# Power.net
KiCad netlist of a schematic drawn in Altium Designer
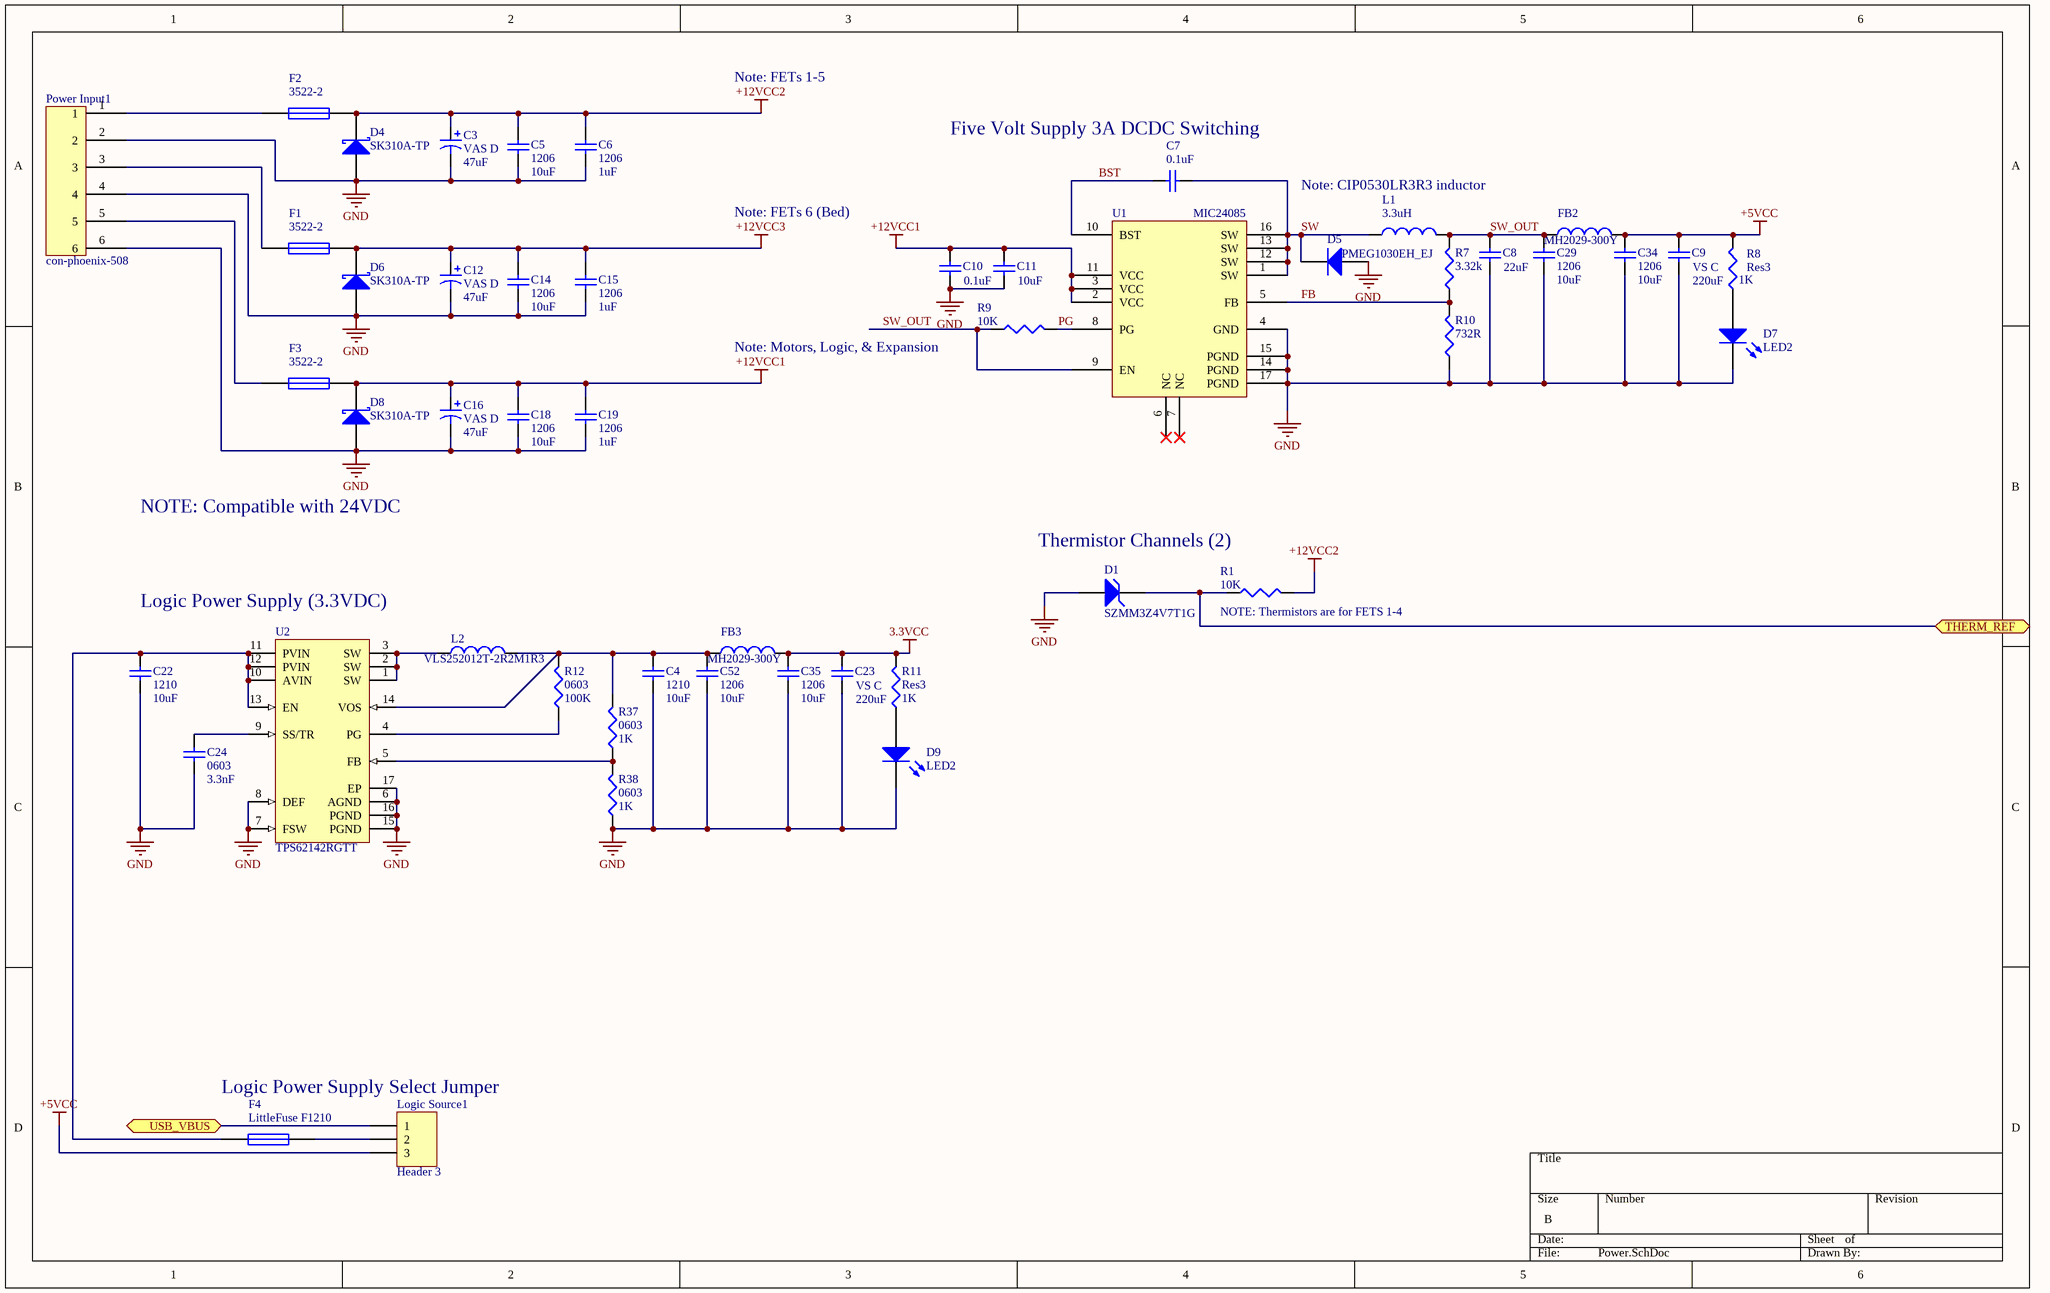
[diagram p0: Power.SchDoc]

(export (version "E")
  (design (tool "Eeschema 10.0.6"))
  (components
    (comp (ref "C3")
      (value "VAS D")
      (footprint "Panasonic VS D")
      (description "Polarized Capacitor (Radial)")
      (fields (field (name "ALTIUM_VALUE") "47uF") (field (name "PUBLISHER") "Altium Limited"))
      (libsource (lib "Miscellaneous Devices") (part "Cap Pol1"))
    )
    (comp (ref "C4")
      (value "1210")
      (footprint "C1210")
      (description "Capacitor (Semiconductor SIM Model)")
      (fields (field (name "ALTIUM_VALUE") "10uF") (field (name "PUBLISHER") "Altium Limited"))
      (libsource (lib "Miscellaneous Devices") (part "Cap Semi"))
    )
    (comp (ref "C5")
      (value "1206")
      (footprint "C1206")
      (description "Capacitor (Semiconductor SIM Model)")
      (fields (field (name "ALTIUM_VALUE") "10uF") (field (name "PUBLISHER") "Altium Limited"))
      (libsource (lib "Miscellaneous Devices") (part "Cap Semi"))
    )
    (comp (ref "C6")
      (value "1206")
      (footprint "C1206")
      (description "Capacitor (Semiconductor SIM Model)")
      (fields (field (name "ALTIUM_VALUE") "1uF") (field (name "PUBLISHER") "Altium Limited"))
      (libsource (lib "Miscellaneous Devices") (part "Cap Semi"))
    )
    (comp (ref "C7")
      (value "0.1uF")
      (footprint "1608[0603]")
      (description "Capacitor (Semiconductor SIM Model)")
      (fields (field (name "Comment") "Cap Semi") (field (name "PUBLISHER") "Altium Limited"))
      (libsource (lib "Miscellaneous Devices") (part "Cap Semi"))
    )
    (comp (ref "C8")
      (value "22uF")
      (footprint "C1206")
      (description "Capacitor (Semiconductor SIM Model)")
      (fields (field (name "Comment") "Cap Semi") (field (name "PUBLISHER") "Altium Limited"))
      (libsource (lib "Miscellaneous Devices") (part "Cap Semi"))
    )
    (comp (ref "C9")
      (value "VS C")
      (footprint "Panasonic VS C")
      (description "Capacitor (Semiconductor SIM Model)")
      (fields (field (name "ALTIUM_VALUE") "220uF") (field (name "PUBLISHER") "Altium Limited"))
      (libsource (lib "Miscellaneous Devices") (part "Cap Semi"))
    )
    (comp (ref "C10")
      (value "0.1uF")
      (footprint "C1206")
      (description "Capacitor (Semiconductor SIM Model)")
      (fields (field (name "Comment") "Cap Semi") (field (name "PUBLISHER") "Altium Limited"))
      (libsource (lib "Miscellaneous Devices") (part "Cap Semi"))
    )
    (comp (ref "C11")
      (value "10uF")
      (footprint "1608[0603]")
      (description "Capacitor (Semiconductor SIM Model)")
      (fields (field (name "Comment") "Cap Semi") (field (name "PUBLISHER") "Altium Limited"))
      (libsource (lib "Miscellaneous Devices") (part "Cap Semi"))
    )
    (comp (ref "C12")
      (value "VAS D")
      (footprint "Panasonic VS D")
      (description "Polarized Capacitor (Radial)")
      (fields (field (name "ALTIUM_VALUE") "47uF") (field (name "PUBLISHER") "Altium Limited"))
      (libsource (lib "Miscellaneous Devices") (part "Cap Pol1"))
    )
    (comp (ref "C14")
      (value "1206")
      (footprint "C1206")
      (description "Capacitor (Semiconductor SIM Model)")
      (fields (field (name "ALTIUM_VALUE") "10uF") (field (name "PUBLISHER") "Altium Limited"))
      (libsource (lib "Miscellaneous Devices") (part "Cap Semi"))
    )
    (comp (ref "C15")
      (value "1206")
      (footprint "C1206")
      (description "Capacitor (Semiconductor SIM Model)")
      (fields (field (name "ALTIUM_VALUE") "1uF") (field (name "PUBLISHER") "Altium Limited"))
      (libsource (lib "Miscellaneous Devices") (part "Cap Semi"))
    )
    (comp (ref "C16")
      (value "VAS D")
      (footprint "Panasonic VS D")
      (description "Polarized Capacitor (Radial)")
      (fields (field (name "ALTIUM_VALUE") "47uF") (field (name "PUBLISHER") "Altium Limited"))
      (libsource (lib "Miscellaneous Devices") (part "Cap Pol1"))
    )
    (comp (ref "C18")
      (value "1206")
      (footprint "C1206")
      (description "Capacitor (Semiconductor SIM Model)")
      (fields (field (name "ALTIUM_VALUE") "10uF") (field (name "PUBLISHER") "Altium Limited"))
      (libsource (lib "Miscellaneous Devices") (part "Cap Semi"))
    )
    (comp (ref "C19")
      (value "1206")
      (footprint "C1206")
      (description "Capacitor (Semiconductor SIM Model)")
      (fields (field (name "ALTIUM_VALUE") "1uF") (field (name "PUBLISHER") "Altium Limited"))
      (libsource (lib "Miscellaneous Devices") (part "Cap Semi"))
    )
    (comp (ref "C22")
      (value "1210")
      (footprint "C1210")
      (description "Capacitor (Semiconductor SIM Model)")
      (fields (field (name "ALTIUM_VALUE") "10uF") (field (name "PUBLISHER") "Altium Limited"))
      (libsource (lib "Miscellaneous Devices") (part "Cap Semi"))
    )
    (comp (ref "C23")
      (value "VS C")
      (footprint "Panasonic VS C")
      (description "Capacitor (Semiconductor SIM Model)")
      (fields (field (name "ALTIUM_VALUE") "220uF") (field (name "PUBLISHER") "Altium Limited"))
      (libsource (lib "Miscellaneous Devices") (part "Cap Semi"))
    )
    (comp (ref "C24")
      (value "0603")
      (footprint "1608[0603]")
      (description "Capacitor (Semiconductor SIM Model)")
      (fields (field (name "ALTIUM_VALUE") "3.3nF") (field (name "PUBLISHER") "Altium Limited"))
      (libsource (lib "Miscellaneous Devices") (part "Cap Semi"))
    )
    (comp (ref "C29")
      (value "1206")
      (footprint "C1206")
      (description "Capacitor (Semiconductor SIM Model)")
      (fields (field (name "ALTIUM_VALUE") "10uF") (field (name "PUBLISHER") "Altium Limited"))
      (libsource (lib "Miscellaneous Devices") (part "Cap Semi"))
    )
    (comp (ref "C34")
      (value "1206")
      (footprint "C1206")
      (description "Capacitor (Semiconductor SIM Model)")
      (fields (field (name "ALTIUM_VALUE") "10uF") (field (name "PUBLISHER") "Altium Limited"))
      (libsource (lib "Miscellaneous Devices") (part "Cap Semi"))
    )
    (comp (ref "C35")
      (value "1206")
      (footprint "C1206")
      (description "Capacitor (Semiconductor SIM Model)")
      (fields (field (name "ALTIUM_VALUE") "10uF") (field (name "PUBLISHER") "Altium Limited"))
      (libsource (lib "Miscellaneous Devices") (part "Cap Semi"))
    )
    (comp (ref "C52")
      (value "1206")
      (footprint "C1206")
      (description "Capacitor (Semiconductor SIM Model)")
      (fields (field (name "ALTIUM_VALUE") "10uF") (field (name "PUBLISHER") "Altium Limited"))
      (libsource (lib "Miscellaneous Devices") (part "Cap Semi"))
    )
    (comp (ref "D1")
      (value "SZMM3Z4V7T1G")
      (footprint "SZMM3Z4V7T1G")
      (description "Zener Diode")
      (fields (field (name "PUBLISHER") "Altium Limited"))
      (libsource (lib "Miscellaneous Devices") (part "D Zener"))
    )
    (comp (ref "D4")
      (value "SK310A-TP")
      (footprint "SK310A-TP")
      (description "Schottky Diode")
      (fields (field (name "PUBLISHER") "Altium Limited"))
      (libsource (lib "Miscellaneous Devices") (part "D Schottky"))
    )
    (comp (ref "D5")
      (value "PMEG1030EH_EJ")
      (footprint "PMEG1030EH_EJ")
      (description "Default Diode")
      (fields (field (name "PUBLISHER") "Altium Limited"))
      (libsource (lib "ZMBo Schematic Library") (part "PMEG1030EH_EJ"))
    )
    (comp (ref "D6")
      (value "SK310A-TP")
      (footprint "SK310A-TP")
      (description "Schottky Diode")
      (fields (field (name "PUBLISHER") "Altium Limited"))
      (libsource (lib "Miscellaneous Devices") (part "D Schottky"))
    )
    (comp (ref "D7")
      (value "LED2")
      (footprint "SM 0805 polarized")
      (description "Typical RED, GREEN, YELLOW, AMBER GaAs LED")
      (fields (field (name "PUBLISHER") "Altium Limited"))
      (libsource (lib "Miscellaneous Devices") (part "LED2"))
    )
    (comp (ref "D8")
      (value "SK310A-TP")
      (footprint "SK310A-TP")
      (description "Schottky Diode")
      (fields (field (name "PUBLISHER") "Altium Limited"))
      (libsource (lib "Miscellaneous Devices") (part "D Schottky"))
    )
    (comp (ref "D9")
      (value "LED2")
      (footprint "SM 0805 polarized")
      (description "Typical RED, GREEN, YELLOW, AMBER GaAs LED")
      (fields (field (name "PUBLISHER") "Altium Limited"))
      (libsource (lib "Miscellaneous Devices") (part "LED2"))
    )
    (comp (ref "F1")
      (value "3522-2")
      (footprint "3522-2")
      (description "Fuse")
      (fields (field (name "PUBLISHER") "Altium Limited"))
      (libsource (lib "Miscellaneous Devices") (part "Fuse 1"))
    )
    (comp (ref "F2")
      (value "3522-2")
      (footprint "3522-2")
      (description "Fuse")
      (fields (field (name "PUBLISHER") "Altium Limited"))
      (libsource (lib "Miscellaneous Devices") (part "Fuse 1"))
    )
    (comp (ref "F3")
      (value "3522-2")
      (footprint "3522-2")
      (description "Fuse")
      (fields (field (name "PUBLISHER") "Altium Limited"))
      (libsource (lib "Miscellaneous Devices") (part "Fuse 1"))
    )
    (comp (ref "F4")
      (value "LittleFuse F1210")
      (footprint "F1210_M")
      (description "Fuse")
      (fields (field (name "PUBLISHER") "Altium Limited"))
      (libsource (lib "Miscellaneous Devices") (part "Fuse 1"))
    )
    (comp (ref "FB2")
      (value "MH2029-300Y")
      (footprint "SM 0805 - gap trimmed")
      (description "Inductor")
      (fields (field (name "PUBLISHER") "Altium Limited"))
      (libsource (lib "Miscellaneous Devices") (part "Inductor"))
    )
    (comp (ref "FB3")
      (value "MH2029-300Y")
      (footprint "SM 0805 - gap trimmed")
      (description "Inductor")
      (fields (field (name "PUBLISHER") "Altium Limited"))
      (libsource (lib "Miscellaneous Devices") (part "Inductor"))
    )
    (comp (ref "L1")
      (value "3.3uH")
      (footprint "CIP0530LR3R3")
      (description "Inductor")
      (fields (field (name "PUBLISHER") "Altium Limited"))
      (libsource (lib "Miscellaneous Devices") (part "Inductor"))
    )
    (comp (ref "L2")
      (value "VLS252012T-2R2M1R3")
      (footprint "VLS252012T-2R2M1R3")
      (description "Inductor")
      (fields (field (name "PUBLISHER") "Altium Limited"))
      (libsource (lib "Miscellaneous Devices") (part "Inductor"))
    )
    (comp (ref "Logic Source1")
      (value "Header 3")
      (footprint "HDR1X3")
      (description "Header, 3-Pin")
      (fields (field (name "PUBLISHER") "Altium Limited"))
      (libsource (lib "Miscellaneous Connectors") (part "Header 3"))
    )
    (comp (ref "Power Input1")
      (value "con-phoenix-508")
      (footprint "MSTBV6")
      (libsource (lib "RADMBo Schematic Library") (part "con-phoenix-508"))
    )
    (comp (ref "R1")
      (value "10K")
      (footprint "J1-0603")
      (description "Resistor")
      (fields (field (name "Comment") "Res3") (field (name "PUBLISHER") "Altium Limited"))
      (libsource (lib "Miscellaneous Devices") (part "Res3"))
    )
    (comp (ref "R7")
      (value "3.32k")
      (footprint "J1-0603")
      (description "Resistor")
      (fields (field (name "Comment") "Res3") (field (name "PUBLISHER") "Altium Limited"))
      (libsource (lib "Miscellaneous Devices") (part "Res3"))
    )
    (comp (ref "R8")
      (value "Res3")
      (footprint "SM 0805 - gap trimmed")
      (description "Resistor")
      (fields (field (name "ALTIUM_VALUE") "1K") (field (name "PUBLISHER") "Altium Limited"))
      (libsource (lib "Miscellaneous Devices") (part "Res3"))
    )
    (comp (ref "R9")
      (value "10K")
      (footprint "J1-0603")
      (description "Resistor")
      (fields (field (name "Comment") "Res3") (field (name "PUBLISHER") "Altium Limited"))
      (libsource (lib "Miscellaneous Devices") (part "Res3"))
    )
    (comp (ref "R10")
      (value "732R")
      (footprint "J1-0603")
      (description "Resistor")
      (fields (field (name "Comment") "Res3") (field (name "PUBLISHER") "Altium Limited"))
      (libsource (lib "Miscellaneous Devices") (part "Res3"))
    )
    (comp (ref "R11")
      (value "Res3")
      (footprint "SM 0805 - gap trimmed")
      (description "Resistor")
      (fields (field (name "ALTIUM_VALUE") "1K") (field (name "PUBLISHER") "Altium Limited"))
      (libsource (lib "Miscellaneous Devices") (part "Res3"))
    )
    (comp (ref "R12")
      (value "0603")
      (footprint "J1-0603")
      (description "Resistor")
      (fields (field (name "ALTIUM_VALUE") "100K") (field (name "PUBLISHER") "Altium Limited"))
      (libsource (lib "Miscellaneous Devices") (part "Res3"))
    )
    (comp (ref "R37")
      (value "0603")
      (footprint "J1-0603")
      (description "Resistor")
      (fields (field (name "ALTIUM_VALUE") "1K") (field (name "PUBLISHER") "Altium Limited"))
      (libsource (lib "Miscellaneous Devices") (part "Res3"))
    )
    (comp (ref "R38")
      (value "0603")
      (footprint "J1-0603")
      (description "Resistor")
      (fields (field (name "ALTIUM_VALUE") "1K") (field (name "PUBLISHER") "Altium Limited"))
      (libsource (lib "Miscellaneous Devices") (part "Res3"))
    )
    (comp (ref "U1")
      (value "MIC24085")
      (footprint "MIC24085-AYML")
      (libsource (lib "Adams Altium Library") (part "MIC24085"))
    )
    (comp (ref "U2")
      (value "TPS62142RGTT")
      (footprint "RGT16-1700X1700TP")
      (fields (field (name "MANUFACTURER") "Texas Instruments"))
      (libsource (lib "TI Power Management Step-Down Regulator") (part "TPS62142RGTT"))
    )
  )
  (nets
    (net (code "1") (name "+5VCC") (class "Default")
      (node (ref "C34") (pin "1") (pinfunction "1_1") (pintype "passive"))
      (node (ref "C9") (pin "1") (pinfunction "1_1") (pintype "passive"))
      (node (ref "FB2") (pin "2") (pinfunction "2_2") (pintype "passive"))
      (node (ref "Logic Source1") (pin "3") (pinfunction "3_3") (pintype "passive"))
      (node (ref "R8") (pin "2") (pinfunction "2_2") (pintype "passive"))
    )
    (net (code "2") (name "+12VCC1") (class "Default")
      (node (ref "C10") (pin "2") (pinfunction "2_2") (pintype "passive"))
      (node (ref "C11") (pin "2") (pinfunction "2_2") (pintype "passive"))
      (node (ref "C16") (pin "1") (pinfunction "1_1") (pintype "passive"))
      (node (ref "C18") (pin "2") (pinfunction "2_2") (pintype "passive"))
      (node (ref "C19") (pin "2") (pinfunction "2_2") (pintype "passive"))
      (node (ref "D8") (pin "2") (pinfunction "K_2") (pintype "passive"))
      (node (ref "F3") (pin "2") (pinfunction "2_2") (pintype "passive"))
      (node (ref "U1") (pin "11") (pinfunction "VCC_11") (pintype "passive"))
      (node (ref "U1") (pin "2") (pinfunction "VCC_2") (pintype "passive"))
      (node (ref "U1") (pin "3") (pinfunction "VCC_3") (pintype "passive"))
    )
    (net (code "3") (name "+12VCC2") (class "Default")
      (node (ref "C3") (pin "1") (pinfunction "1_1") (pintype "passive"))
      (node (ref "C5") (pin "2") (pinfunction "2_2") (pintype "passive"))
      (node (ref "C6") (pin "2") (pinfunction "2_2") (pintype "passive"))
      (node (ref "D4") (pin "2") (pinfunction "K_2") (pintype "passive"))
      (node (ref "F2") (pin "2") (pinfunction "2_2") (pintype "passive"))
      (node (ref "R1") (pin "2") (pinfunction "2_2") (pintype "passive"))
    )
    (net (code "4") (name "+12VCC3") (class "Default")
      (node (ref "C12") (pin "1") (pinfunction "1_1") (pintype "passive"))
      (node (ref "C14") (pin "2") (pinfunction "2_2") (pintype "passive"))
      (node (ref "C15") (pin "2") (pinfunction "2_2") (pintype "passive"))
      (node (ref "D6") (pin "2") (pinfunction "K_2") (pintype "passive"))
      (node (ref "F1") (pin "2") (pinfunction "2_2") (pintype "passive"))
    )
    (net (code "5") (name "/BST") (class "Default")
      (node (ref "C7") (pin "2") (pinfunction "2_2") (pintype "passive"))
      (node (ref "U1") (pin "10") (pinfunction "BST_10") (pintype "passive"))
    )
    (net (code "6") (name "/FB") (class "Default")
      (node (ref "R10") (pin "2") (pinfunction "2_2") (pintype "passive"))
      (node (ref "R7") (pin "1") (pinfunction "1_1") (pintype "passive"))
      (node (ref "U1") (pin "5") (pinfunction "FB_5") (pintype "passive"))
    )
    (net (code "7") (name "/PG") (class "Default")
      (node (ref "R9") (pin "2") (pinfunction "2_2") (pintype "passive"))
      (node (ref "U1") (pin "8") (pinfunction "PG_8") (pintype "passive"))
    )
    (net (code "8") (name "/SW") (class "Default")
      (node (ref "C7") (pin "1") (pinfunction "1_1") (pintype "passive"))
      (node (ref "D5") (pin "2") (pinfunction "K_2") (pintype "passive"))
      (node (ref "L1") (pin "1") (pinfunction "1_1") (pintype "passive"))
      (node (ref "U1") (pin "1") (pinfunction "SW_1") (pintype "passive"))
      (node (ref "U1") (pin "12") (pinfunction "SW_12") (pintype "passive"))
      (node (ref "U1") (pin "13") (pinfunction "SW_13") (pintype "passive"))
      (node (ref "U1") (pin "16") (pinfunction "SW_16") (pintype "passive"))
    )
    (net (code "9") (name "/SW_OUT") (class "Default")
      (node (ref "C29") (pin "1") (pinfunction "1_1") (pintype "passive"))
      (node (ref "C8") (pin "2") (pinfunction "2_2") (pintype "passive"))
      (node (ref "FB2") (pin "1") (pinfunction "1_1") (pintype "passive"))
      (node (ref "L1") (pin "2") (pinfunction "2_2") (pintype "passive"))
      (node (ref "R7") (pin "2") (pinfunction "2_2") (pintype "passive"))
      (node (ref "R9") (pin "1") (pinfunction "1_1") (pintype "passive"))
      (node (ref "U1") (pin "9") (pinfunction "EN_9") (pintype "passive"))
    )
    (net (code "10") (name "/THERM_REF") (class "Default")
      (node (ref "D1") (pin "2") (pinfunction "K_2") (pintype "passive"))
      (node (ref "R1") (pin "1") (pinfunction "1_1") (pintype "passive"))
    )
    (net (code "11") (name "/USB_VBUS") (class "Default")
      (node (ref "Logic Source1") (pin "1") (pinfunction "1_1") (pintype "passive"))
    )
    (net (code "12") (name "3.3VCC") (class "Default")
      (node (ref "C23") (pin "1") (pinfunction "1_1") (pintype "passive"))
      (node (ref "C35") (pin "1") (pinfunction "1_1") (pintype "passive"))
      (node (ref "FB3") (pin "2") (pinfunction "2_2") (pintype "passive"))
      (node (ref "R11") (pin "2") (pinfunction "2_2") (pintype "passive"))
    )
    (net (code "13") (name "GND") (class "Default")
      (node (ref "C10") (pin "1") (pinfunction "1_1") (pintype "passive"))
      (node (ref "C11") (pin "1") (pinfunction "1_1") (pintype "passive"))
      (node (ref "C12") (pin "2") (pinfunction "2_2") (pintype "passive"))
      (node (ref "C14") (pin "1") (pinfunction "1_1") (pintype "passive"))
      (node (ref "C15") (pin "1") (pinfunction "1_1") (pintype "passive"))
      (node (ref "C16") (pin "2") (pinfunction "2_2") (pintype "passive"))
      (node (ref "C18") (pin "1") (pinfunction "1_1") (pintype "passive"))
      (node (ref "C19") (pin "1") (pinfunction "1_1") (pintype "passive"))
      (node (ref "C22") (pin "2") (pinfunction "2_2") (pintype "passive"))
      (node (ref "C23") (pin "2") (pinfunction "2_2") (pintype "passive"))
      (node (ref "C24") (pin "1") (pinfunction "1_1") (pintype "passive"))
      (node (ref "C29") (pin "2") (pinfunction "2_2") (pintype "passive"))
      (node (ref "C3") (pin "2") (pinfunction "2_2") (pintype "passive"))
      (node (ref "C34") (pin "2") (pinfunction "2_2") (pintype "passive"))
      (node (ref "C35") (pin "2") (pinfunction "2_2") (pintype "passive"))
      (node (ref "C4") (pin "2") (pinfunction "2_2") (pintype "passive"))
      (node (ref "C5") (pin "1") (pinfunction "1_1") (pintype "passive"))
      (node (ref "C52") (pin "2") (pinfunction "2_2") (pintype "passive"))
      (node (ref "C6") (pin "1") (pinfunction "1_1") (pintype "passive"))
      (node (ref "C8") (pin "1") (pinfunction "1_1") (pintype "passive"))
      (node (ref "C9") (pin "2") (pinfunction "2_2") (pintype "passive"))
      (node (ref "D1") (pin "1") (pinfunction "A_1") (pintype "passive"))
      (node (ref "D4") (pin "1") (pinfunction "A_1") (pintype "passive"))
      (node (ref "D5") (pin "1") (pinfunction "A_1") (pintype "passive"))
      (node (ref "D6") (pin "1") (pinfunction "A_1") (pintype "passive"))
      (node (ref "D7") (pin "1") (pinfunction "A_1") (pintype "passive"))
      (node (ref "D8") (pin "1") (pinfunction "A_1") (pintype "passive"))
      (node (ref "D9") (pin "1") (pinfunction "A_1") (pintype "passive"))
      (node (ref "Power Input1") (pin "2") (pinfunction "2_2") (pintype "passive"))
      (node (ref "Power Input1") (pin "4") (pinfunction "4_4") (pintype "passive"))
      (node (ref "Power Input1") (pin "6") (pinfunction "6_6") (pintype "passive"))
      (node (ref "R10") (pin "1") (pinfunction "1_1") (pintype "passive"))
      (node (ref "R38") (pin "1") (pinfunction "1_1") (pintype "passive"))
      (node (ref "U1") (pin "14") (pinfunction "PGND_14") (pintype "passive"))
      (node (ref "U1") (pin "15") (pinfunction "PGND_15") (pintype "passive"))
      (node (ref "U1") (pin "17") (pinfunction "PGND_17") (pintype "passive"))
      (node (ref "U1") (pin "4") (pinfunction "GND_4") (pintype "passive"))
      (node (ref "U2") (pin "15") (pinfunction "PGND_15") (pintype "power_in"))
      (node (ref "U2") (pin "16") (pinfunction "PGND_16") (pintype "power_in"))
      (node (ref "U2") (pin "17") (pinfunction "EP_17") (pintype "power_in"))
      (node (ref "U2") (pin "6") (pinfunction "AGND_6") (pintype "power_in"))
      (node (ref "U2") (pin "7") (pinfunction "FSW_7") (pintype "input"))
      (node (ref "U2") (pin "8") (pinfunction "DEF_8") (pintype "input"))
    )
    (net (code "14") (name "Net-(D7-K)") (class "Default")
      (node (ref "D7") (pin "2") (pinfunction "K_2") (pintype "passive"))
      (node (ref "R8") (pin "1") (pinfunction "1_1") (pintype "passive"))
    )
    (net (code "15") (name "Net-(D9-K)") (class "Default")
      (node (ref "D9") (pin "2") (pinfunction "K_2") (pintype "passive"))
      (node (ref "R11") (pin "1") (pinfunction "1_1") (pintype "passive"))
    )
    (net (code "16") (name "Net-(F1-Pad1)") (class "Default")
      (node (ref "F1") (pin "1") (pinfunction "1_1") (pintype "passive"))
      (node (ref "Power Input1") (pin "3") (pinfunction "3_3") (pintype "passive"))
    )
    (net (code "17") (name "Net-(F2-Pad1)") (class "Default")
      (node (ref "F2") (pin "1") (pinfunction "1_1") (pintype "passive"))
      (node (ref "Power Input1") (pin "1") (pinfunction "1_1") (pintype "passive"))
    )
    (net (code "18") (name "Net-(F3-Pad1)") (class "Default")
      (node (ref "F3") (pin "1") (pinfunction "1_1") (pintype "passive"))
      (node (ref "Power Input1") (pin "5") (pinfunction "5_5") (pintype "passive"))
    )
    (net (code "19") (name "Net-(F4-Pad2)") (class "Default")
      (node (ref "F4") (pin "2") (pinfunction "2_2") (pintype "passive"))
      (node (ref "Logic Source1") (pin "2") (pinfunction "2_2") (pintype "passive"))
    )
    (net (code "20") (name "Net-(L2-Pad1)") (class "Default")
      (node (ref "L2") (pin "1") (pinfunction "1_1") (pintype "passive"))
      (node (ref "U2") (pin "1") (pinfunction "SW_1") (pintype "power_in"))
      (node (ref "U2") (pin "2") (pinfunction "SW_2") (pintype "power_in"))
      (node (ref "U2") (pin "3") (pinfunction "SW_3") (pintype "power_in"))
    )
    (net (code "21") (name "Net-(U2-AVIN)") (class "Default")
      (node (ref "C22") (pin "1") (pinfunction "1_1") (pintype "passive"))
      (node (ref "F4") (pin "1") (pinfunction "1_1") (pintype "passive"))
      (node (ref "U2") (pin "10") (pinfunction "AVIN_10") (pintype "power_in"))
      (node (ref "U2") (pin "11") (pinfunction "PVIN_11") (pintype "power_in"))
      (node (ref "U2") (pin "12") (pinfunction "PVIN_12") (pintype "power_in"))
      (node (ref "U2") (pin "13") (pinfunction "EN_13") (pintype "input"))
    )
    (net (code "22") (name "Net-(U2-FB)") (class "Default")
      (node (ref "R37") (pin "1") (pinfunction "1_1") (pintype "passive"))
      (node (ref "R38") (pin "2") (pinfunction "2_2") (pintype "passive"))
      (node (ref "U2") (pin "5") (pinfunction "FB_5") (pintype "input"))
    )
    (net (code "23") (name "Net-(U2-PG)") (class "Default")
      (node (ref "R12") (pin "1") (pinfunction "1_1") (pintype "passive"))
      (node (ref "U2") (pin "4") (pinfunction "PG_4") (pintype "tri_state"))
    )
    (net (code "24") (name "Net-(U2-SS{slash}TR)") (class "Default")
      (node (ref "C24") (pin "2") (pinfunction "2_2") (pintype "passive"))
      (node (ref "U2") (pin "9") (pinfunction "SS/TR_9") (pintype "input"))
    )
    (net (code "25") (name "Net-(U2-VOS)") (class "Default")
      (node (ref "C4") (pin "1") (pinfunction "1_1") (pintype "passive"))
      (node (ref "C52") (pin "1") (pinfunction "1_1") (pintype "passive"))
      (node (ref "FB3") (pin "1") (pinfunction "1_1") (pintype "passive"))
      (node (ref "L2") (pin "2") (pinfunction "2_2") (pintype "passive"))
      (node (ref "R12") (pin "2") (pinfunction "2_2") (pintype "passive"))
      (node (ref "R37") (pin "2") (pinfunction "2_2") (pintype "passive"))
      (node (ref "U2") (pin "14") (pinfunction "VOS_14") (pintype "input"))
    )
    (net (code "26") (name "unconnected-(U1-NC-Pad6)") (class "Default")
      (node (ref "U1") (pin "6") (pinfunction "NC_6") (pintype "passive+no_connect"))
    )
    (net (code "27") (name "unconnected-(U1-NC-Pad7)") (class "Default")
      (node (ref "U1") (pin "7") (pinfunction "NC_7") (pintype "passive+no_connect"))
    )
  )
)
